# Teedi_REV_A1.net
KiCad netlist of a schematic drawn in EAGLE
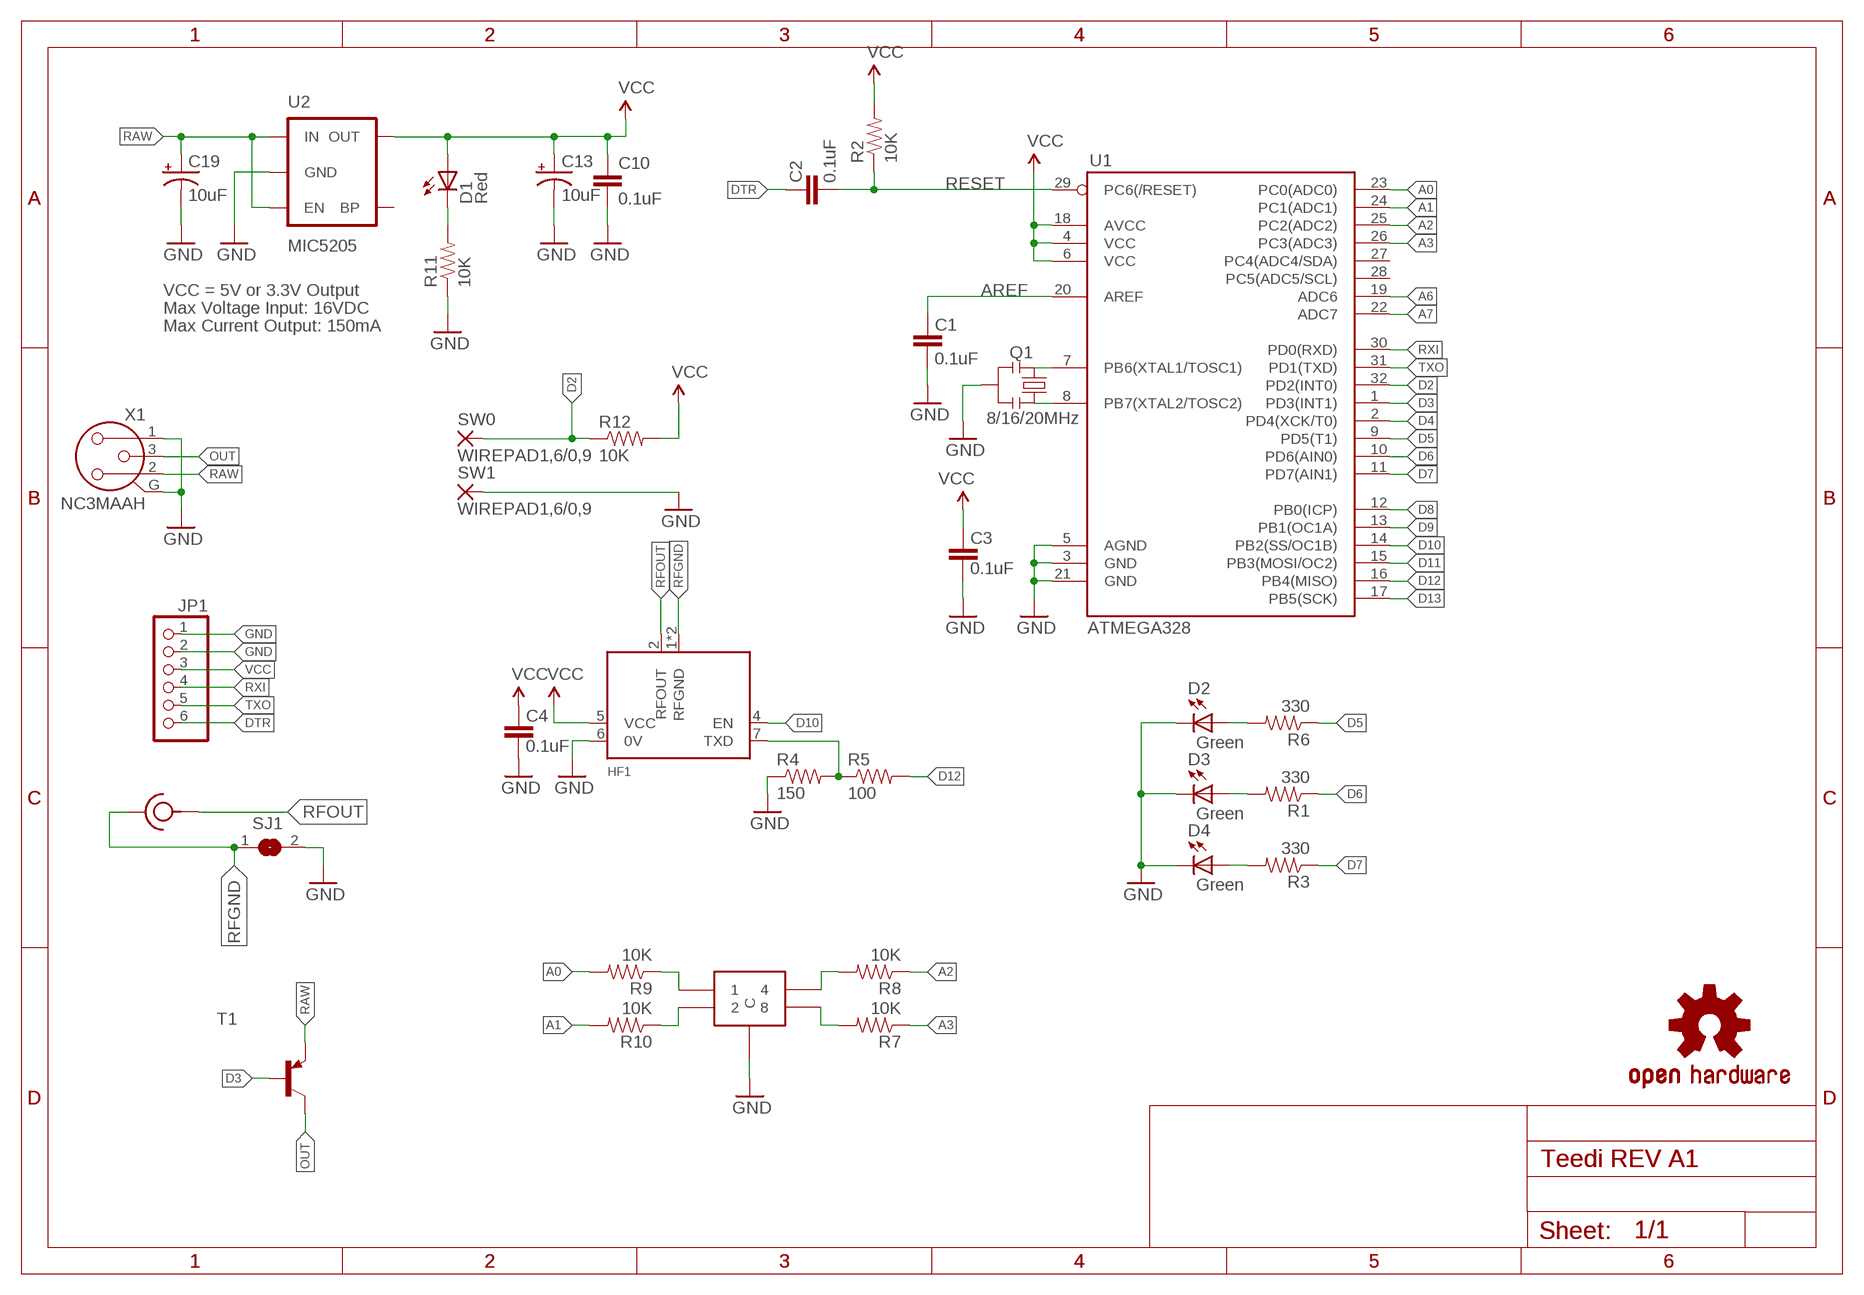
[diagram p0: schematic, sheet 1]

(export (version "E")
  (design (tool "Eeschema 10.0.6"))
  (components
    (comp (ref "C1")
      (value "0.1uF")
      (footprint "eagle-import:0603-CAP")
      (fields (field (name "MF") "MULTICOMP") (field (name "MPN") "MC0603F104Z160CT"))
      (libsource (lib "eagle-import") (part "CAP0603-CAP"))
    )
    (comp (ref "C2")
      (value "0.1uF")
      (footprint "eagle-import:0603-CAP")
      (fields (field (name "MF") "MULTICOMP") (field (name "MPN") "MC0603F104Z160CT"))
      (libsource (lib "eagle-import") (part "CAP0603-CAP"))
    )
    (comp (ref "C3")
      (value "0.1uF")
      (footprint "eagle-import:0603-CAP")
      (fields (field (name "MF") "MULTICOMP") (field (name "MPN") "MC0603F104Z160CT"))
      (libsource (lib "eagle-import") (part "CAP0603-CAP"))
    )
    (comp (ref "C4")
      (value "0.1uF")
      (footprint "eagle-import:0603-CAP")
      (fields (field (name "MF") "MULTICOMP") (field (name "MPN") "MC0603F104Z160CT"))
      (libsource (lib "eagle-import") (part "CAP0603-CAP"))
    )
    (comp (ref "C10")
      (value "0.1uF")
      (footprint "eagle-import:0603-CAP")
      (fields (field (name "MF") "MULTICOMP") (field (name "MPN") "MC0603F104Z160CT"))
      (libsource (lib "eagle-import") (part "CAP0603-CAP"))
    )
    (comp (ref "C13")
      (value "10uF")
      (footprint "eagle-import:EIA3216")
      (fields (field (name "MF") "MULTICOMP") (field (name "MPN") "MCCTA106M006"))
      (libsource (lib "eagle-import") (part "CAP_POL1206"))
    )
    (comp (ref "C19")
      (value "10uF")
      (footprint "eagle-import:EIA3216")
      (fields (field (name "MF") "MULTICOMP") (field (name "MPN") "MCCTA106M006"))
      (libsource (lib "eagle-import") (part "CAP_POL1206"))
    )
    (comp (ref "D1")
      (value "Red")
      (footprint "eagle-import:0603-LED-ALT1")
      (fields (field (name "MF") "MULTICOMP") (field (name "MPN") "MCL-S290SRC"))
      (libsource (lib "eagle-import") (part "LED"))
    )
    (comp (ref "D2")
      (value "Green")
      (footprint "eagle-import:0603-LED-ALT1")
      (fields (field (name "MF") "MULTICOMP") (field (name "MPN") "703-0109"))
      (libsource (lib "eagle-import") (part "LED"))
    )
    (comp (ref "D3")
      (value "Green")
      (footprint "eagle-import:0603-LED-ALT1")
      (fields (field (name "MF") "MULTICOMP") (field (name "MPN") "703-0109"))
      (libsource (lib "eagle-import") (part "LED"))
    )
    (comp (ref "D4")
      (value "Green")
      (footprint "eagle-import:0603-LED-ALT1")
      (fields (field (name "MF") "MULTICOMP") (field (name "MPN") "703-0109"))
      (libsource (lib "eagle-import") (part "LED"))
    )
    (comp (ref "HF1")
      (value "TX2A-433-64")
      (footprint "eagle-import:TX2A")
      (fields (field (name "MF") "RADIOMETRIX"))
      (libsource (lib "eagle-import") (part "TX2A-433-64"))
    )
    (comp (ref "JP1")
      (value "PINHD-1X6")
      (footprint "eagle-import:1X06")
      (fields (field (name "MF") "MULTICOMP") (field (name "MPN") "MC34751"))
      (libsource (lib "eagle-import") (part "PINHD-1X6"))
    )
    (comp (ref "Q1")
      (value "8/16/20MHz")
      (footprint "eagle-import:RESONATOR-SMD-1_1")
      (fields (field (name "MF") "MURATA") (field (name "MPN") "CSTCE8M00G55Z-R0"))
      (libsource (lib "eagle-import") (part "RESONATOR1{colon}1"))
    )
    (comp (ref "R1")
      (value "330")
      (footprint "eagle-import:0603-RES")
      (fields (field (name "MF") "MULTICOMP") (field (name "MPN") "MCWR06X3300FTL"))
      (libsource (lib "eagle-import") (part "RESISTOR0603-RES"))
    )
    (comp (ref "R2")
      (value "10K")
      (footprint "eagle-import:0603-RES")
      (fields (field (name "MF") "MULTICOMP") (field (name "MPN") "MCHP03W8F1002T5E"))
      (libsource (lib "eagle-import") (part "RESISTOR0603-RES"))
    )
    (comp (ref "R3")
      (value "330")
      (footprint "eagle-import:0603-RES")
      (fields (field (name "MF") "MULTICOMP") (field (name "MPN") "MCWR06X3300FTL"))
      (libsource (lib "eagle-import") (part "RESISTOR0603-RES"))
    )
    (comp (ref "R4")
      (value "150")
      (footprint "eagle-import:0603-RES")
      (fields (field (name "MF") "MULTICOMP") (field (name "MPN") "MCWR06X1500FTL"))
      (libsource (lib "eagle-import") (part "RESISTOR0603-RES"))
    )
    (comp (ref "R5")
      (value "100")
      (footprint "eagle-import:0603-RES")
      (fields (field (name "MF") "MULTICOMP") (field (name "MPN") "MCWR06X1000FTL"))
      (libsource (lib "eagle-import") (part "RESISTOR0603-RES"))
    )
    (comp (ref "R6")
      (value "330")
      (footprint "eagle-import:0603-RES")
      (fields (field (name "MF") "MULTICOMP") (field (name "MPN") "MCWR06X3300FTL"))
      (libsource (lib "eagle-import") (part "RESISTOR0603-RES"))
    )
    (comp (ref "R7")
      (value "10K")
      (footprint "eagle-import:0603-RES")
      (fields (field (name "MF") "MULTICOMP") (field (name "MPN") "MCHP03W8F1002T5E"))
      (libsource (lib "eagle-import") (part "RESISTOR0603-RES"))
    )
    (comp (ref "R8")
      (value "10K")
      (footprint "eagle-import:0603-RES")
      (fields (field (name "MF") "MULTICOMP") (field (name "MPN") "MCHP03W8F1002T5E"))
      (libsource (lib "eagle-import") (part "RESISTOR0603-RES"))
    )
    (comp (ref "R9")
      (value "10K")
      (footprint "eagle-import:0603-RES")
      (fields (field (name "MF") "MULTICOMP") (field (name "MPN") "MCHP03W8F1002T5E"))
      (libsource (lib "eagle-import") (part "RESISTOR0603-RES"))
    )
    (comp (ref "R10")
      (value "10K")
      (footprint "eagle-import:0603-RES")
      (fields (field (name "MF") "MULTICOMP") (field (name "MPN") "MCHP03W8F1002T5E"))
      (libsource (lib "eagle-import") (part "RESISTOR0603-RES"))
    )
    (comp (ref "R11")
      (value "10K")
      (footprint "eagle-import:0603-RES")
      (fields (field (name "MF") "MULTICOMP") (field (name "MPN") "MCHP03W8F1002T5E"))
      (libsource (lib "eagle-import") (part "RESISTOR0603-RES"))
    )
    (comp (ref "R12")
      (value "10K")
      (footprint "eagle-import:0603-RES")
      (fields (field (name "MF") "MULTICOMP") (field (name "MPN") "MCHP03W8F1002T5E"))
      (libsource (lib "eagle-import") (part "RESISTOR0603-RES"))
    )
    (comp (ref "RF1")
      (value "132203")
      (footprint "eagle-import:132203")
      (fields (field (name "MF") "AMPHENOL CONNEX"))
      (libsource (lib "eagle-import") (part "132203"))
    )
    (comp (ref "SJ1") (value "SJ") (footprint "eagle-import:SJ") (libsource (lib "eagle-import") (part "SJ")))
    (comp (ref "SW0")
      (value "WIREPAD1,6/0,9")
      (footprint "eagle-import:1,6_0,9")
      (libsource (lib "eagle-import") (part "WIREPAD1,6/0,9"))
    )
    (comp (ref "SW1")
      (value "WIREPAD1,6/0,9")
      (footprint "eagle-import:1,6_0,9")
      (libsource (lib "eagle-import") (part "WIREPAD1,6/0,9"))
    )
    (comp (ref "T1")
      (value "-PNP-SOT23-BCE")
      (footprint "eagle-import:SOT23-BCE")
      (fields (field (name "MF") "NXP") (field (name "MPN") "BC807-25"))
      (libsource (lib "eagle-import") (part "-PNP-SOT23-BCE"))
    )
    (comp (ref "U$3")
      (value "OSHW-LOGOS")
      (footprint "eagle-import:OSHW-LOGO-S")
      (libsource (lib "eagle-import") (part "OSHW-LOGOS"))
    )
    (comp (ref "U$5")
      (value "PT65-101-L508")
      (footprint "eagle-import:PT65-101-L508")
      (fields (field (name "MF") "APEM"))
      (libsource (lib "eagle-import") (part "PT65-101-?L508"))
    )
    (comp (ref "U1")
      (value "ATMEGA328")
      (footprint "eagle-import:TQFP32-08")
      (fields (field (name "MF") "ATMEL") (field (name "MPN") "ATMEGA328-AUR"))
      (libsource (lib "eagle-import") (part "ATMEGA168"))
    )
    (comp (ref "U2")
      (value "MIC5205")
      (footprint "eagle-import:SOT23-5")
      (fields (field (name "MF") "MICREL SEMICONDUCTOR") (field (name "MPN") "MIC5205-3.0YM5 TR"))
      (libsource (lib "eagle-import") (part "V_REG_LDOSMD"))
    )
    (comp (ref "X1")
      (value "NC3MAAH")
      (footprint "eagle-import:NC3MAH")
      (fields (field (name "MF") "NEUTRIK"))
      (libsource (lib "eagle-import") (part "NC3MAAH"))
    )
  )
  (nets
    (net (code "1") (name "/AREF") (class "Default")
      (node (ref "C1") (pin "2") (pinfunction "2_2") (pintype "passive"))
      (node (ref "U1") (pin "20") (pinfunction "AREF_20") (pintype "bidirectional"))
    )
    (net (code "2") (name "/RESET") (class "Default")
      (node (ref "C2") (pin "1") (pinfunction "1_1") (pintype "passive"))
      (node (ref "R2") (pin "1") (pinfunction "1_1") (pintype "passive"))
      (node (ref "U1") (pin "29") (pinfunction "PC6(/RESET)_29") (pintype "bidirectional"))
    )
    (net (code "3") (name "A0") (class "Default")
      (node (ref "R9") (pin "2") (pinfunction "2_2") (pintype "passive"))
      (node (ref "U1") (pin "23") (pinfunction "PC0(ADC0)_23") (pintype "bidirectional"))
    )
    (net (code "4") (name "A1") (class "Default")
      (node (ref "R10") (pin "2") (pinfunction "2_2") (pintype "passive"))
      (node (ref "U1") (pin "24") (pinfunction "PC1(ADC1)_24") (pintype "bidirectional"))
    )
    (net (code "5") (name "A2") (class "Default")
      (node (ref "R8") (pin "1") (pinfunction "1_1") (pintype "passive"))
      (node (ref "U1") (pin "25") (pinfunction "PC2(ADC2)_25") (pintype "bidirectional"))
    )
    (net (code "6") (name "A3") (class "Default")
      (node (ref "R7") (pin "1") (pinfunction "1_1") (pintype "passive"))
      (node (ref "U1") (pin "26") (pinfunction "PC3(ADC3)_26") (pintype "bidirectional"))
    )
    (net (code "7") (name "A6") (class "Default")
      (node (ref "U1") (pin "19") (pinfunction "ADC6_19") (pintype "bidirectional"))
    )
    (net (code "8") (name "A7") (class "Default")
      (node (ref "U1") (pin "22") (pinfunction "ADC7_22") (pintype "bidirectional"))
    )
    (net (code "9") (name "D2") (class "Default")
      (node (ref "R12") (pin "1") (pinfunction "1_1") (pintype "passive"))
      (node (ref "SW0") (pin "1") (pinfunction "P_1") (pintype "passive"))
      (node (ref "U1") (pin "32") (pinfunction "PD2(INT0)_32") (pintype "bidirectional"))
    )
    (net (code "10") (name "D3") (class "Default")
      (node (ref "T1") (pin "B") (pinfunction "B_B") (pintype "passive"))
      (node (ref "U1") (pin "1") (pinfunction "PD3(INT1)_1") (pintype "bidirectional"))
    )
    (net (code "11") (name "D4") (class "Default")
      (node (ref "U1") (pin "2") (pinfunction "PD4(XCK/T0)_2") (pintype "bidirectional"))
    )
    (net (code "12") (name "D5") (class "Default")
      (node (ref "R6") (pin "1") (pinfunction "1_1") (pintype "passive"))
      (node (ref "U1") (pin "9") (pinfunction "PD5(T1)_9") (pintype "bidirectional"))
    )
    (net (code "13") (name "D6") (class "Default")
      (node (ref "R1") (pin "1") (pinfunction "1_1") (pintype "passive"))
      (node (ref "U1") (pin "10") (pinfunction "PD6(AIN0)_10") (pintype "bidirectional"))
    )
    (net (code "14") (name "D7") (class "Default")
      (node (ref "R3") (pin "1") (pinfunction "1_1") (pintype "passive"))
      (node (ref "U1") (pin "11") (pinfunction "PD7(AIN1)_11") (pintype "bidirectional"))
    )
    (net (code "15") (name "D8") (class "Default")
      (node (ref "U1") (pin "12") (pinfunction "PB0(ICP)_12") (pintype "bidirectional"))
    )
    (net (code "16") (name "D9") (class "Default")
      (node (ref "U1") (pin "13") (pinfunction "PB1(OC1A)_13") (pintype "bidirectional"))
    )
    (net (code "17") (name "D10") (class "Default")
      (node (ref "HF1") (pin "4") (pinfunction "EN_4") (pintype "input"))
      (node (ref "U1") (pin "14") (pinfunction "PB2(SS/OC1B)_14") (pintype "bidirectional"))
    )
    (net (code "18") (name "D11") (class "Default")
      (node (ref "U1") (pin "15") (pinfunction "PB3(MOSI/OC2)_15") (pintype "bidirectional"))
    )
    (net (code "19") (name "D12") (class "Default")
      (node (ref "R5") (pin "2") (pinfunction "2_2") (pintype "passive"))
      (node (ref "U1") (pin "16") (pinfunction "PB4(MISO)_16") (pintype "bidirectional"))
    )
    (net (code "20") (name "D13") (class "Default")
      (node (ref "U1") (pin "17") (pinfunction "PB5(SCK)_17") (pintype "bidirectional"))
    )
    (net (code "21") (name "DTR") (class "Default")
      (node (ref "C2") (pin "2") (pinfunction "2_2") (pintype "passive"))
      (node (ref "JP1") (pin "6") (pinfunction "6_6") (pintype "passive"))
    )
    (net (code "22") (name "GND") (class "Default")
      (node (ref "C1") (pin "1") (pinfunction "1_1") (pintype "passive"))
      (node (ref "C10") (pin "2") (pinfunction "2_2") (pintype "passive"))
      (node (ref "C13") (pin "C") (pinfunction "-_C") (pintype "passive"))
      (node (ref "C19") (pin "C") (pinfunction "-_C") (pintype "passive"))
      (node (ref "C3") (pin "1") (pinfunction "1_1") (pintype "passive"))
      (node (ref "C4") (pin "1") (pinfunction "1_1") (pintype "passive"))
      (node (ref "D2") (pin "C") (pinfunction "C_C") (pintype "passive"))
      (node (ref "D3") (pin "C") (pinfunction "C_C") (pintype "passive"))
      (node (ref "D4") (pin "C") (pinfunction "C_C") (pintype "passive"))
      (node (ref "HF1") (pin "6") (pinfunction "0V_6") (pintype "power_in"))
      (node (ref "JP1") (pin "1") (pinfunction "1_1") (pintype "passive"))
      (node (ref "JP1") (pin "2") (pinfunction "2_2") (pintype "passive"))
      (node (ref "Q1") (pin "2") (pinfunction "2_2") (pintype "passive"))
      (node (ref "R11") (pin "1") (pinfunction "1_1") (pintype "passive"))
      (node (ref "R4") (pin "1") (pinfunction "1_1") (pintype "passive"))
      (node (ref "SJ1") (pin "2") (pinfunction "2_2") (pintype "passive"))
      (node (ref "SW1") (pin "1") (pinfunction "P_1") (pintype "passive"))
      (node (ref "U$5") (pin "C1") (pinfunction "C_C1") (pintype "bidirectional"))
      (node (ref "U$5") (pin "C2") (pinfunction "C_C2") (pintype "bidirectional"))
      (node (ref "U1") (pin "21") (pinfunction "GND_21") (pintype "bidirectional"))
      (node (ref "U1") (pin "3") (pinfunction "GND_3") (pintype "bidirectional"))
      (node (ref "U1") (pin "5") (pinfunction "AGND_5") (pintype "bidirectional"))
      (node (ref "U2") (pin "2") (pinfunction "GND_2") (pintype "input"))
      (node (ref "X1") (pin "1") (pinfunction "1_1") (pintype "passive"))
      (node (ref "X1") (pin "G") (pinfunction "G_G") (pintype "passive"))
    )
    (net (code "23") (name "Net-(D1-PadC)") (class "Default")
      (node (ref "D1") (pin "C") (pinfunction "C_C") (pintype "passive"))
      (node (ref "R11") (pin "2") (pinfunction "2_2") (pintype "passive"))
    )
    (net (code "24") (name "Net-(D2-PadA)") (class "Default")
      (node (ref "D2") (pin "A") (pinfunction "A_A") (pintype "passive"))
      (node (ref "R6") (pin "2") (pinfunction "2_2") (pintype "passive"))
    )
    (net (code "25") (name "Net-(D3-PadA)") (class "Default")
      (node (ref "D3") (pin "A") (pinfunction "A_A") (pintype "passive"))
      (node (ref "R1") (pin "2") (pinfunction "2_2") (pintype "passive"))
    )
    (net (code "26") (name "Net-(D4-PadA)") (class "Default")
      (node (ref "D4") (pin "A") (pinfunction "A_A") (pintype "passive"))
      (node (ref "R3") (pin "2") (pinfunction "2_2") (pintype "passive"))
    )
    (net (code "27") (name "Net-(HF1-TXD)") (class "Default")
      (node (ref "HF1") (pin "7") (pinfunction "TXD_7") (pintype "input"))
      (node (ref "R4") (pin "2") (pinfunction "2_2") (pintype "passive"))
      (node (ref "R5") (pin "1") (pinfunction "1_1") (pintype "passive"))
    )
    (net (code "28") (name "Net-(R7-Pad2)") (class "Default")
      (node (ref "R7") (pin "2") (pinfunction "2_2") (pintype "passive"))
      (node (ref "U$5") (pin "8") (pinfunction "8_8") (pintype "bidirectional"))
    )
    (net (code "29") (name "Net-(R8-Pad2)") (class "Default")
      (node (ref "R8") (pin "2") (pinfunction "2_2") (pintype "passive"))
      (node (ref "U$5") (pin "4") (pinfunction "4_4") (pintype "bidirectional"))
    )
    (net (code "30") (name "Net-(R9-Pad1)") (class "Default")
      (node (ref "R9") (pin "1") (pinfunction "1_1") (pintype "passive"))
      (node (ref "U$5") (pin "1") (pinfunction "1_1") (pintype "bidirectional"))
    )
    (net (code "31") (name "Net-(R10-Pad1)") (class "Default")
      (node (ref "R10") (pin "1") (pinfunction "1_1") (pintype "passive"))
      (node (ref "U$5") (pin "2") (pinfunction "2_2") (pintype "bidirectional"))
    )
    (net (code "32") (name "Net-(U1-PB6(XTAL1{slash}TOSC1))") (class "Default")
      (node (ref "Q1") (pin "1") (pinfunction "1_1") (pintype "passive"))
      (node (ref "U1") (pin "7") (pinfunction "PB6(XTAL1/TOSC1)_7") (pintype "bidirectional"))
    )
    (net (code "33") (name "Net-(U1-PB7(XTAL2{slash}TOSC2))") (class "Default")
      (node (ref "Q1") (pin "3") (pinfunction "3_3") (pintype "passive"))
      (node (ref "U1") (pin "8") (pinfunction "PB7(XTAL2/TOSC2)_8") (pintype "bidirectional"))
    )
    (net (code "34") (name "OUT") (class "Default")
      (node (ref "T1") (pin "C") (pinfunction "C_C") (pintype "passive"))
      (node (ref "X1") (pin "3") (pinfunction "3_3") (pintype "passive"))
    )
    (net (code "35") (name "RAW") (class "Default")
      (node (ref "C19") (pin "A") (pinfunction "+_A") (pintype "passive"))
      (node (ref "T1") (pin "E") (pinfunction "E_E") (pintype "passive"))
      (node (ref "U2") (pin "1") (pinfunction "IN_1") (pintype "input"))
      (node (ref "U2") (pin "3") (pinfunction "EN_3") (pintype "input"))
      (node (ref "X1") (pin "2") (pinfunction "2_2") (pintype "passive"))
    )
    (net (code "36") (name "RFGND") (class "Default")
      (node (ref "HF1") (pin "1") (pinfunction "RFGND_1") (pintype "output"))
      (node (ref "HF1") (pin "3") (pinfunction "RFGND_3") (pintype "output"))
      (node (ref "RF1") (pin "G1") (pinfunction "GND_G1") (pintype "bidirectional"))
      (node (ref "RF1") (pin "G2") (pinfunction "GND_G2") (pintype "bidirectional"))
      (node (ref "RF1") (pin "G3") (pinfunction "GND_G3") (pintype "bidirectional"))
      (node (ref "RF1") (pin "G4") (pinfunction "GND_G4") (pintype "bidirectional"))
      (node (ref "SJ1") (pin "1") (pinfunction "1_1") (pintype "passive"))
    )
    (net (code "37") (name "RFOUT") (class "Default")
      (node (ref "HF1") (pin "2") (pinfunction "RFOUT_2") (pintype "output"))
      (node (ref "RF1") (pin "P") (pinfunction "RF_P") (pintype "bidirectional"))
    )
    (net (code "38") (name "RXI") (class "Default")
      (node (ref "JP1") (pin "4") (pinfunction "4_4") (pintype "passive"))
      (node (ref "U1") (pin "30") (pinfunction "PD0(RXD)_30") (pintype "bidirectional"))
    )
    (net (code "39") (name "TXO") (class "Default")
      (node (ref "JP1") (pin "5") (pinfunction "5_5") (pintype "passive"))
      (node (ref "U1") (pin "31") (pinfunction "PD1(TXD)_31") (pintype "bidirectional"))
    )
    (net (code "40") (name "VCC") (class "Default")
      (node (ref "C10") (pin "1") (pinfunction "1_1") (pintype "passive"))
      (node (ref "C13") (pin "A") (pinfunction "+_A") (pintype "passive"))
      (node (ref "C3") (pin "2") (pinfunction "2_2") (pintype "passive"))
      (node (ref "C4") (pin "2") (pinfunction "2_2") (pintype "passive"))
      (node (ref "D1") (pin "A") (pinfunction "A_A") (pintype "passive"))
      (node (ref "HF1") (pin "5") (pinfunction "VCC_5") (pintype "power_in"))
      (node (ref "JP1") (pin "3") (pinfunction "3_3") (pintype "passive"))
      (node (ref "R12") (pin "2") (pinfunction "2_2") (pintype "passive"))
      (node (ref "R2") (pin "2") (pinfunction "2_2") (pintype "passive"))
      (node (ref "U1") (pin "18") (pinfunction "AVCC_18") (pintype "bidirectional"))
      (node (ref "U1") (pin "4") (pinfunction "VCC_4") (pintype "bidirectional"))
      (node (ref "U1") (pin "6") (pinfunction "VCC_6") (pintype "bidirectional"))
      (node (ref "U2") (pin "5") (pinfunction "OUT_5") (pintype "passive"))
    )
    (net (code "41") (name "unconnected-(U1-PC4(ADC4{slash}SDA)-Pad27)") (class "Default")
      (node (ref "U1") (pin "27") (pinfunction "PC4(ADC4/SDA)_27") (pintype "bidirectional"))
    )
    (net (code "42") (name "unconnected-(U1-PC5(ADC5{slash}SCL)-Pad28)") (class "Default")
      (node (ref "U1") (pin "28") (pinfunction "PC5(ADC5/SCL)_28") (pintype "bidirectional"))
    )
    (net (code "43") (name "unconnected-(U2-BP-Pad4)") (class "Default")
      (node (ref "U2") (pin "4") (pinfunction "BP_4") (pintype "input"))
    )
  )
)
